# MI_06_07_08_MCU_Rev_3_0.net
KiCad netlist of a schematic drawn in Altium Designer
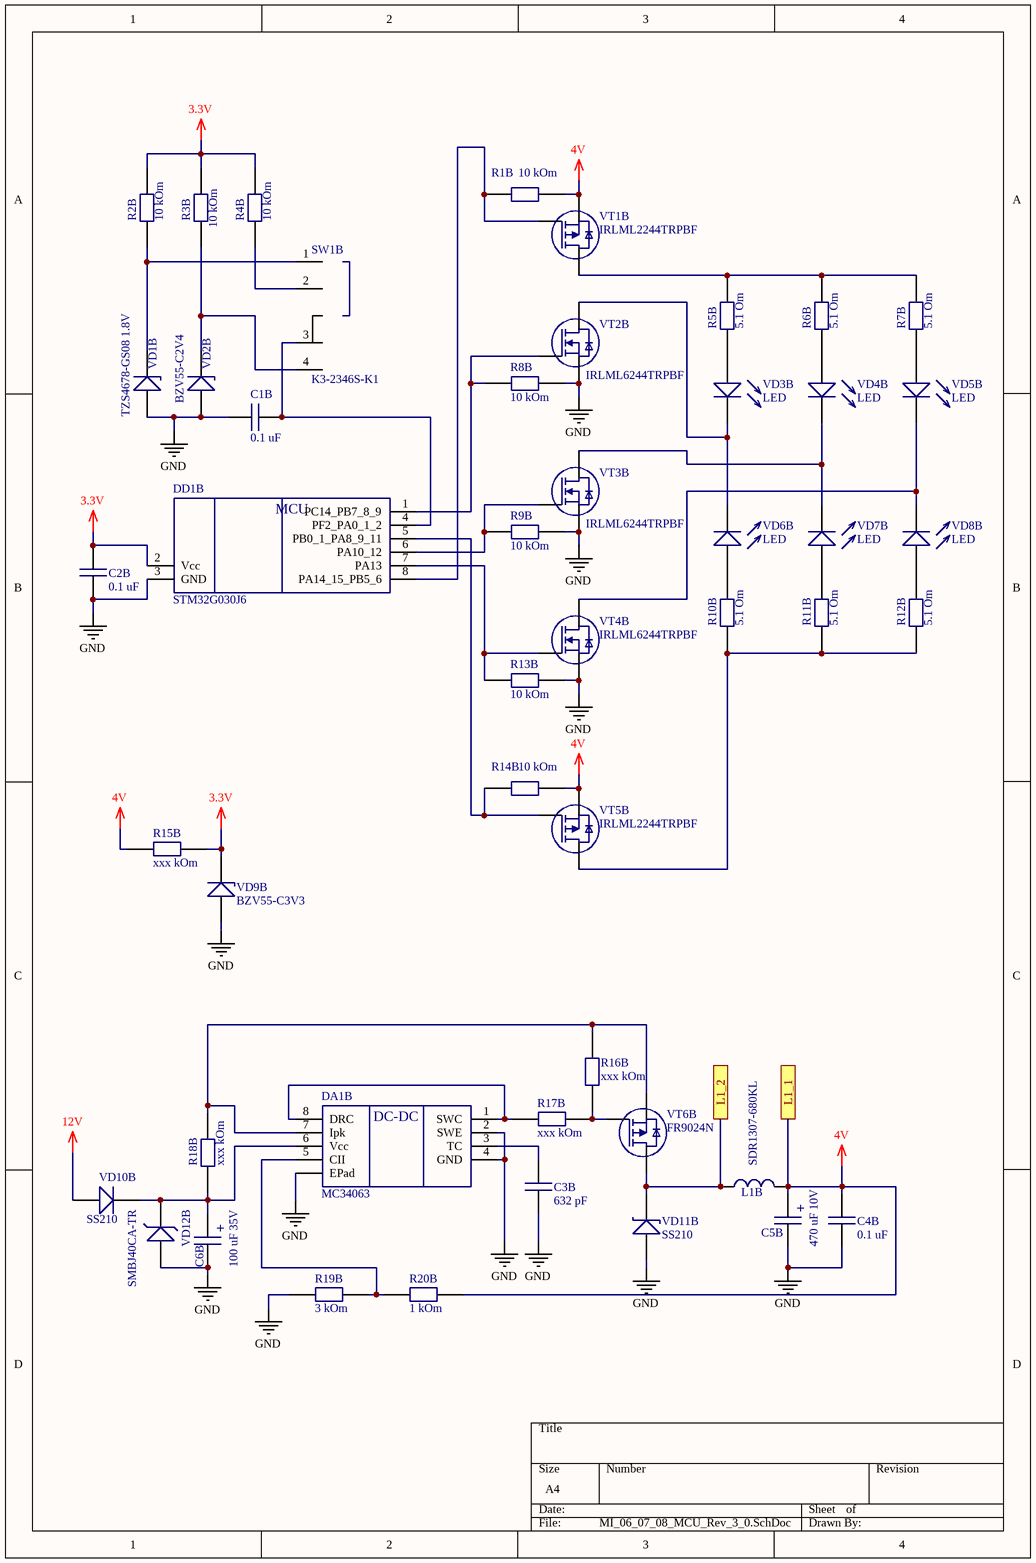
[diagram p0: MI_06_07_08_MCU_Rev_3_0.SchDoc]

(export (version "E")
  (design (tool "Eeschema 10.0.6"))
  (components
    (comp (ref "C1B")
      (value "0.1 uF")
      (footprint "CAP1206")
      (fields (field (name "Comment") "Capacitor"))
      (libsource (lib "my_library") (part "Capacitor"))
    )
    (comp (ref "C2B")
      (value "0.1 uF")
      (footprint "CAP1206")
      (fields (field (name "Comment") "Capacitor"))
      (libsource (lib "my_library") (part "Capacitor"))
    )
    (comp (ref "C3B")
      (value "632 pF")
      (footprint "CAP1206")
      (fields (field (name "Comment") "Capacitor"))
      (libsource (lib "my_library") (part "Capacitor"))
    )
    (comp (ref "C4B")
      (value "0.1 uF")
      (footprint "CAP1206")
      (fields (field (name "Comment") "Capacitor"))
      (libsource (lib "my_library") (part "Capacitor"))
    )
    (comp (ref "C5B")
      (value "470 uF 10V")
      (footprint "CAP6.3x7.7")
      (fields (field (name "Comment") "Capacitor_Polar"))
      (libsource (lib "my_library") (part "Capacitor_Polar"))
    )
    (comp (ref "C6B")
      (value "100 uF 35V")
      (footprint "CAP6.3x7.7")
      (fields (field (name "Comment") "Capacitor_Polar"))
      (libsource (lib "my_library") (part "Capacitor_Polar"))
    )
    (comp (ref "DA1B")
      (value "MC34063")
      (footprint "SOIC-8-EPad")
      (libsource (lib "my_library") (part "MC34063"))
    )
    (comp (ref "DD1B")
      (value "STM32G030J6")
      (footprint "SOIC-8")
      (libsource (lib "my_library") (part "STM32G030J6"))
    )
    (comp (ref "L1B")
      (value "SDR1307-680KL")
      (footprint "SDR1307")
      (fields (field (name "Comment") "coil"))
      (libsource (lib "my_library") (part "coil"))
    )
    (comp (ref "R1B")
      (value "10 kOm")
      (footprint "RES1206")
      (fields (field (name "Comment") "Resistor"))
      (libsource (lib "my_library") (part "Resistor"))
    )
    (comp (ref "R2B")
      (value "10 kOm")
      (footprint "RES1206")
      (fields (field (name "Comment") "Resistor"))
      (libsource (lib "my_library") (part "Resistor"))
    )
    (comp (ref "R3B")
      (value "10 kOm")
      (footprint "RES1206")
      (fields (field (name "Comment") "Resistor"))
      (libsource (lib "my_library") (part "Resistor"))
    )
    (comp (ref "R4B")
      (value "10 kOm")
      (footprint "RES1206")
      (fields (field (name "Comment") "Resistor"))
      (libsource (lib "my_library") (part "Resistor"))
    )
    (comp (ref "R5B")
      (value "5.1 Om")
      (footprint "RES1206")
      (fields (field (name "Comment") "Resistor"))
      (libsource (lib "my_library") (part "Resistor"))
    )
    (comp (ref "R6B")
      (value "5.1 Om")
      (footprint "RES1206")
      (fields (field (name "Comment") "Resistor"))
      (libsource (lib "my_library") (part "Resistor"))
    )
    (comp (ref "R7B")
      (value "5.1 Om")
      (footprint "RES1206")
      (fields (field (name "Comment") "Resistor"))
      (libsource (lib "my_library") (part "Resistor"))
    )
    (comp (ref "R8B")
      (value "10 kOm")
      (footprint "RES1206")
      (fields (field (name "Comment") "Resistor"))
      (libsource (lib "my_library") (part "Resistor"))
    )
    (comp (ref "R9B")
      (value "10 kOm")
      (footprint "RES1206")
      (fields (field (name "Comment") "Resistor"))
      (libsource (lib "my_library") (part "Resistor"))
    )
    (comp (ref "R10B")
      (value "5.1 Om")
      (footprint "RES1206")
      (fields (field (name "Comment") "Resistor"))
      (libsource (lib "my_library") (part "Resistor"))
    )
    (comp (ref "R11B")
      (value "5.1 Om")
      (footprint "RES1206")
      (fields (field (name "Comment") "Resistor"))
      (libsource (lib "my_library") (part "Resistor"))
    )
    (comp (ref "R12B")
      (value "5.1 Om")
      (footprint "RES1206")
      (fields (field (name "Comment") "Resistor"))
      (libsource (lib "my_library") (part "Resistor"))
    )
    (comp (ref "R13B")
      (value "10 kOm")
      (footprint "RES1206")
      (fields (field (name "Comment") "Resistor"))
      (libsource (lib "my_library") (part "Resistor"))
    )
    (comp (ref "R14B")
      (value "10 kOm")
      (footprint "RES1206")
      (fields (field (name "Comment") "Resistor"))
      (libsource (lib "my_library") (part "Resistor"))
    )
    (comp (ref "R15B")
      (value "xxx kOm")
      (footprint "RES1206")
      (fields (field (name "Comment") "Resistor"))
      (libsource (lib "my_library") (part "Resistor"))
    )
    (comp (ref "R16B")
      (value "xxx kOm")
      (footprint "RES1206")
      (fields (field (name "Comment") "Resistor"))
      (libsource (lib "my_library") (part "Resistor"))
    )
    (comp (ref "R17B")
      (value "xxx kOm")
      (footprint "RES1206")
      (fields (field (name "Comment") "Resistor"))
      (libsource (lib "my_library") (part "Resistor"))
    )
    (comp (ref "R18B")
      (value "xxx kOm")
      (footprint "RES1206")
      (fields (field (name "Comment") "Resistor"))
      (libsource (lib "my_library") (part "Resistor"))
    )
    (comp (ref "R19B")
      (value "3 kOm")
      (footprint "RES1206")
      (fields (field (name "Comment") "Resistor"))
      (libsource (lib "my_library") (part "Resistor"))
    )
    (comp (ref "R20B")
      (value "1 kOm")
      (footprint "RES1206")
      (fields (field (name "Comment") "Resistor"))
      (libsource (lib "my_library") (part "Resistor"))
    )
    (comp (ref "SW1B")
      (value "K3-2346S-K1")
      (footprint "К3-2346S-K1")
      (fields (field (name "Comment") "mks13c02"))
      (libsource (lib "my_library") (part "mks13c02"))
    )
    (comp (ref "VD1B")
      (value "TZS4678-GS08 1.8V")
      (footprint "minimelf")
      (fields (field (name "Comment") "Zenner"))
      (libsource (lib "my_library") (part "Zenner"))
    )
    (comp (ref "VD2B")
      (value "BZV55-C2V4")
      (footprint "minimelf")
      (fields (field (name "Comment") "Zenner"))
      (libsource (lib "my_library") (part "Zenner"))
    )
    (comp (ref "VD3B") (value "LED") (footprint "LED_MAJAK2") (libsource (lib "my_library") (part "LED")))
    (comp (ref "VD4B") (value "LED") (footprint "LED_MAJAK2") (libsource (lib "my_library") (part "LED")))
    (comp (ref "VD5B") (value "LED") (footprint "LED_MAJAK2") (libsource (lib "my_library") (part "LED")))
    (comp (ref "VD6B") (value "LED") (footprint "LED_MAJAK2") (libsource (lib "my_library") (part "LED")))
    (comp (ref "VD7B") (value "LED") (footprint "LED_MAJAK2") (libsource (lib "my_library") (part "LED")))
    (comp (ref "VD8B") (value "LED") (footprint "LED_MAJAK2") (libsource (lib "my_library") (part "LED")))
    (comp (ref "VD9B")
      (value "BZV55-C3V3")
      (footprint "minimelf")
      (fields (field (name "Comment") "Zenner"))
      (libsource (lib "") (part "Zenner_1"))
    )
    (comp (ref "VD10B")
      (value "SS210")
      (footprint "SMB1")
      (fields (field (name "Comment") "Diode"))
      (libsource (lib "my_library") (part "Diode"))
    )
    (comp (ref "VD11B")
      (value "SS210")
      (footprint "SMB1")
      (fields (field (name "Comment") "Schottky"))
      (libsource (lib "my_library") (part "Schottky"))
    )
    (comp (ref "VD12B")
      (value "SMBJ40CA-TR")
      (footprint "SMB1")
      (fields (field (name "Comment") "Suppressor"))
      (libsource (lib "my_library") (part "Suppressor"))
    )
    (comp (ref "VT1B")
      (value "IRLML2244TRPBF")
      (footprint "SOT 23")
      (fields (field (name "Comment") "MOSFET-P"))
      (libsource (lib "my_library") (part "MOSFET-P"))
    )
    (comp (ref "VT2B")
      (value "IRLML6244TRPBF")
      (footprint "SOT 23")
      (fields (field (name "Comment") "MOSFET-N"))
      (libsource (lib "my_library") (part "MOSFET-N"))
    )
    (comp (ref "VT3B")
      (value "IRLML6244TRPBF")
      (footprint "SOT 23")
      (fields (field (name "Comment") "MOSFET-N"))
      (libsource (lib "my_library") (part "MOSFET-N"))
    )
    (comp (ref "VT4B")
      (value "IRLML6244TRPBF")
      (footprint "SOT 23")
      (fields (field (name "Comment") "MOSFET-N"))
      (libsource (lib "my_library") (part "MOSFET-N"))
    )
    (comp (ref "VT5B")
      (value "IRLML2244TRPBF")
      (footprint "SOT 23")
      (fields (field (name "Comment") "MOSFET-P"))
      (libsource (lib "my_library") (part "MOSFET-P"))
    )
    (comp (ref "VT6B")
      (value "FR9024N")
      (footprint "D PAK")
      (fields (field (name "Comment") "MOSFET-P"))
      (libsource (lib "my_library") (part "MOSFET-P"))
    )
  )
  (nets
    (net (code "1") (name "/L1_2") (class "Default")
      (node (ref "L1B") (pin "1") (pinfunction "1_1") (pintype "passive"))
      (node (ref "VD11B") (pin "1") (pinfunction "1_1") (pintype "passive"))
      (node (ref "VT6B") (pin "D") (pintype "passive"))
    )
    (net (code "2") (name "3.3V") (class "Default")
      (node (ref "C2B") (pin "2") (pinfunction "2_2") (pintype "passive"))
      (node (ref "DD1B") (pin "2") (pinfunction "Vcc_2") (pintype "passive"))
      (node (ref "R15B") (pin "1") (pinfunction "1_1") (pintype "passive"))
      (node (ref "R2B") (pin "1") (pinfunction "1_1") (pintype "passive"))
      (node (ref "R3B") (pin "1") (pinfunction "1_1") (pintype "passive"))
      (node (ref "R4B") (pin "1") (pinfunction "1_1") (pintype "passive"))
      (node (ref "VD9B") (pin "1") (pinfunction "1_1") (pintype "passive"))
    )
    (net (code "3") (name "4V") (class "Default")
      (node (ref "C4B") (pin "1") (pinfunction "1_1") (pintype "passive"))
      (node (ref "C5B") (pin "1") (pinfunction "1_1") (pintype "passive"))
      (node (ref "L1B") (pin "2") (pinfunction "2_2") (pintype "passive"))
      (node (ref "R14B") (pin "2") (pinfunction "2_2") (pintype "passive"))
      (node (ref "R15B") (pin "2") (pinfunction "2_2") (pintype "passive"))
      (node (ref "R1B") (pin "2") (pinfunction "2_2") (pintype "passive"))
      (node (ref "R20B") (pin "2") (pinfunction "2_2") (pintype "passive"))
      (node (ref "VT1B") (pin "S") (pintype "passive"))
      (node (ref "VT5B") (pin "S") (pintype "passive"))
    )
    (net (code "4") (name "12V") (class "Default")
      (node (ref "VD10B") (pin "1") (pinfunction "1_1") (pintype "passive"))
    )
    (net (code "5") (name "GND") (class "Default")
      (node (ref "C1B") (pin "2") (pinfunction "2_2") (pintype "passive"))
      (node (ref "C2B") (pin "1") (pinfunction "1_1") (pintype "passive"))
      (node (ref "C3B") (pin "2") (pinfunction "2_2") (pintype "passive"))
      (node (ref "C4B") (pin "2") (pinfunction "2_2") (pintype "passive"))
      (node (ref "C5B") (pin "2") (pinfunction "2_2") (pintype "passive"))
      (node (ref "C6B") (pin "2") (pinfunction "2_2") (pintype "passive"))
      (node (ref "DA1B") (pin "0") (pinfunction "EPad_0") (pintype "passive"))
      (node (ref "DA1B") (pin "2") (pinfunction "SWE_2") (pintype "passive"))
      (node (ref "DA1B") (pin "4") (pinfunction "GND_4") (pintype "passive"))
      (node (ref "DD1B") (pin "3") (pinfunction "GND_3") (pintype "passive"))
      (node (ref "R13B") (pin "2") (pinfunction "2_2") (pintype "passive"))
      (node (ref "R19B") (pin "2") (pinfunction "2_2") (pintype "passive"))
      (node (ref "R8B") (pin "2") (pinfunction "2_2") (pintype "passive"))
      (node (ref "R9B") (pin "2") (pinfunction "2_2") (pintype "passive"))
      (node (ref "VD11B") (pin "2") (pinfunction "2_2") (pintype "passive"))
      (node (ref "VD12B") (pin "2") (pinfunction "2_2") (pintype "passive"))
      (node (ref "VD1B") (pin "1") (pinfunction "1_1") (pintype "passive"))
      (node (ref "VD2B") (pin "1") (pinfunction "1_1") (pintype "passive"))
      (node (ref "VD9B") (pin "2") (pinfunction "2_2") (pintype "passive"))
      (node (ref "VT2B") (pin "S") (pintype "passive"))
      (node (ref "VT3B") (pin "S") (pintype "passive"))
      (node (ref "VT4B") (pin "S") (pintype "passive"))
    )
    (net (code "6") (name "Net-(DA1B-CII)") (class "Default")
      (node (ref "DA1B") (pin "5") (pinfunction "CII_5") (pintype "passive"))
      (node (ref "R19B") (pin "1") (pinfunction "1_1") (pintype "passive"))
      (node (ref "R20B") (pin "1") (pinfunction "1_1") (pintype "passive"))
    )
    (net (code "7") (name "Net-(DA1B-DRC)") (class "Default")
      (node (ref "DA1B") (pin "1") (pinfunction "SWC_1") (pintype "passive"))
      (node (ref "DA1B") (pin "8") (pinfunction "DRC_8") (pintype "passive"))
      (node (ref "R17B") (pin "2") (pinfunction "2_2") (pintype "passive"))
    )
    (net (code "8") (name "Net-(DA1B-Ipk)") (class "Default")
      (node (ref "DA1B") (pin "7") (pinfunction "Ipk_7") (pintype "passive"))
      (node (ref "R16B") (pin "1") (pinfunction "1_1") (pintype "passive"))
      (node (ref "R18B") (pin "1") (pinfunction "1_1") (pintype "passive"))
      (node (ref "VT6B") (pin "S") (pintype "passive"))
    )
    (net (code "9") (name "Net-(DA1B-TC)") (class "Default")
      (node (ref "C3B") (pin "1") (pinfunction "1_1") (pintype "passive"))
      (node (ref "DA1B") (pin "3") (pinfunction "TC_3") (pintype "passive"))
    )
    (net (code "10") (name "Net-(DA1B-Vcc)") (class "Default")
      (node (ref "C6B") (pin "1") (pinfunction "1_1") (pintype "passive"))
      (node (ref "DA1B") (pin "6") (pinfunction "Vcc_6") (pintype "passive"))
      (node (ref "R18B") (pin "2") (pinfunction "2_2") (pintype "passive"))
      (node (ref "VD10B") (pin "3") (pinfunction "3_3") (pintype "passive"))
      (node (ref "VD12B") (pin "1") (pinfunction "1_1") (pintype "passive"))
    )
    (net (code "11") (name "Net-(DD1B-PA10_12)") (class "Default")
      (node (ref "DD1B") (pin "6") (pinfunction "PA10_12_6") (pintype "passive"))
      (node (ref "R9B") (pin "1") (pinfunction "1_1") (pintype "passive"))
      (node (ref "VT3B") (pin "G") (pintype "passive"))
    )
    (net (code "12") (name "Net-(DD1B-PA13)") (class "Default")
      (node (ref "DD1B") (pin "7") (pinfunction "PA13_7") (pintype "passive"))
      (node (ref "R13B") (pin "1") (pinfunction "1_1") (pintype "passive"))
      (node (ref "VT4B") (pin "G") (pintype "passive"))
    )
    (net (code "13") (name "Net-(DD1B-PA14_15_PB5_6)") (class "Default")
      (node (ref "DD1B") (pin "8") (pinfunction "PA14_15_PB5_6_8") (pintype "passive"))
      (node (ref "R1B") (pin "1") (pinfunction "1_1") (pintype "passive"))
      (node (ref "VT1B") (pin "G") (pintype "passive"))
    )
    (net (code "14") (name "Net-(DD1B-PB0_1_PA8_9_11)") (class "Default")
      (node (ref "DD1B") (pin "5") (pinfunction "PB0_1_PA8_9_11_5") (pintype "passive"))
      (node (ref "R14B") (pin "1") (pinfunction "1_1") (pintype "passive"))
      (node (ref "VT5B") (pin "G") (pintype "passive"))
    )
    (net (code "15") (name "Net-(DD1B-PC14_PB7_8_9)") (class "Default")
      (node (ref "DD1B") (pin "1") (pinfunction "PC14_PB7_8_9_1") (pintype "passive"))
      (node (ref "R8B") (pin "1") (pinfunction "1_1") (pintype "passive"))
      (node (ref "VT2B") (pin "G") (pintype "passive"))
    )
    (net (code "16") (name "Net-(DD1B-PF2_PA0_1_2)") (class "Default")
      (node (ref "C1B") (pin "1") (pinfunction "1_1") (pintype "passive"))
      (node (ref "DD1B") (pin "4") (pinfunction "PF2_PA0_1_2_4") (pintype "passive"))
      (node (ref "SW1B") (pin "3") (pinfunction "3_3") (pintype "passive"))
    )
    (net (code "17") (name "Net-(R2B-Pad2)") (class "Default")
      (node (ref "R2B") (pin "2") (pinfunction "2_2") (pintype "passive"))
      (node (ref "SW1B") (pin "1") (pinfunction "1_1") (pintype "passive"))
      (node (ref "VD1B") (pin "3") (pinfunction "3_3") (pintype "passive"))
    )
    (net (code "18") (name "Net-(R3B-Pad2)") (class "Default")
      (node (ref "R3B") (pin "2") (pinfunction "2_2") (pintype "passive"))
      (node (ref "SW1B") (pin "4") (pinfunction "4_4") (pintype "passive"))
      (node (ref "VD2B") (pin "3") (pinfunction "3_3") (pintype "passive"))
    )
    (net (code "19") (name "Net-(R4B-Pad2)") (class "Default")
      (node (ref "R4B") (pin "2") (pinfunction "2_2") (pintype "passive"))
      (node (ref "SW1B") (pin "2") (pinfunction "2_2") (pintype "passive"))
    )
    (net (code "20") (name "Net-(R5B-Pad1)") (class "Default")
      (node (ref "R5B") (pin "1") (pinfunction "1_1") (pintype "passive"))
      (node (ref "R6B") (pin "1") (pinfunction "1_1") (pintype "passive"))
      (node (ref "R7B") (pin "1") (pinfunction "1_1") (pintype "passive"))
      (node (ref "VT1B") (pin "D") (pintype "passive"))
    )
    (net (code "21") (name "Net-(R5B-Pad2)") (class "Default")
      (node (ref "R5B") (pin "2") (pinfunction "2_2") (pintype "passive"))
      (node (ref "VD3B") (pin "2") (pinfunction "2_2") (pintype "passive"))
    )
    (net (code "22") (name "Net-(R6B-Pad2)") (class "Default")
      (node (ref "R6B") (pin "2") (pinfunction "2_2") (pintype "passive"))
      (node (ref "VD4B") (pin "2") (pinfunction "2_2") (pintype "passive"))
    )
    (net (code "23") (name "Net-(R7B-Pad2)") (class "Default")
      (node (ref "R7B") (pin "2") (pinfunction "2_2") (pintype "passive"))
      (node (ref "VD5B") (pin "2") (pinfunction "2_2") (pintype "passive"))
    )
    (net (code "24") (name "Net-(R10B-Pad1)") (class "Default")
      (node (ref "R10B") (pin "1") (pinfunction "1_1") (pintype "passive"))
      (node (ref "VD6B") (pin "2") (pinfunction "2_2") (pintype "passive"))
    )
    (net (code "25") (name "Net-(R10B-Pad2)") (class "Default")
      (node (ref "R10B") (pin "2") (pinfunction "2_2") (pintype "passive"))
      (node (ref "R11B") (pin "2") (pinfunction "2_2") (pintype "passive"))
      (node (ref "R12B") (pin "2") (pinfunction "2_2") (pintype "passive"))
      (node (ref "VT5B") (pin "D") (pintype "passive"))
    )
    (net (code "26") (name "Net-(R11B-Pad1)") (class "Default")
      (node (ref "R11B") (pin "1") (pinfunction "1_1") (pintype "passive"))
      (node (ref "VD7B") (pin "2") (pinfunction "2_2") (pintype "passive"))
    )
    (net (code "27") (name "Net-(R12B-Pad1)") (class "Default")
      (node (ref "R12B") (pin "1") (pinfunction "1_1") (pintype "passive"))
      (node (ref "VD8B") (pin "2") (pinfunction "2_2") (pintype "passive"))
    )
    (net (code "28") (name "Net-(R16B-Pad2)") (class "Default")
      (node (ref "R16B") (pin "2") (pinfunction "2_2") (pintype "passive"))
      (node (ref "R17B") (pin "1") (pinfunction "1_1") (pintype "passive"))
      (node (ref "VT6B") (pin "G") (pintype "passive"))
    )
    (net (code "29") (name "Net-(VD3B-Pad1)") (class "Default")
      (node (ref "VD3B") (pin "1") (pinfunction "1_1") (pintype "passive"))
      (node (ref "VD6B") (pin "1") (pinfunction "1_1") (pintype "passive"))
      (node (ref "VT2B") (pin "D") (pintype "passive"))
    )
    (net (code "30") (name "Net-(VD4B-Pad1)") (class "Default")
      (node (ref "VD4B") (pin "1") (pinfunction "1_1") (pintype "passive"))
      (node (ref "VD7B") (pin "1") (pinfunction "1_1") (pintype "passive"))
      (node (ref "VT3B") (pin "D") (pintype "passive"))
    )
    (net (code "31") (name "Net-(VD5B-Pad1)") (class "Default")
      (node (ref "VD5B") (pin "1") (pinfunction "1_1") (pintype "passive"))
      (node (ref "VD8B") (pin "1") (pinfunction "1_1") (pintype "passive"))
      (node (ref "VT4B") (pin "D") (pintype "passive"))
    )
  )
)
